# 16ChFNIRS.net
KiCad netlist of a schematic drawn in EAGLE
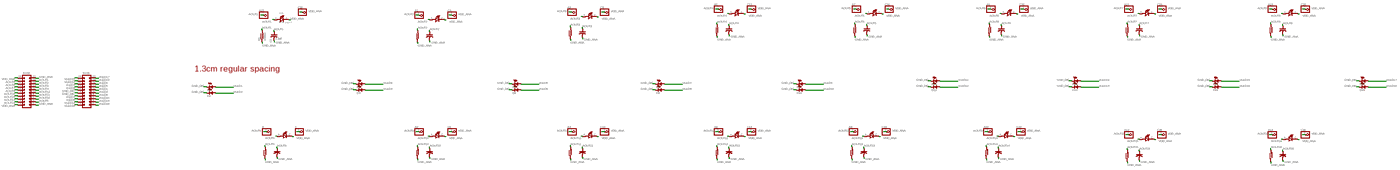
[diagram p0: schematic, sheet 1, overview]
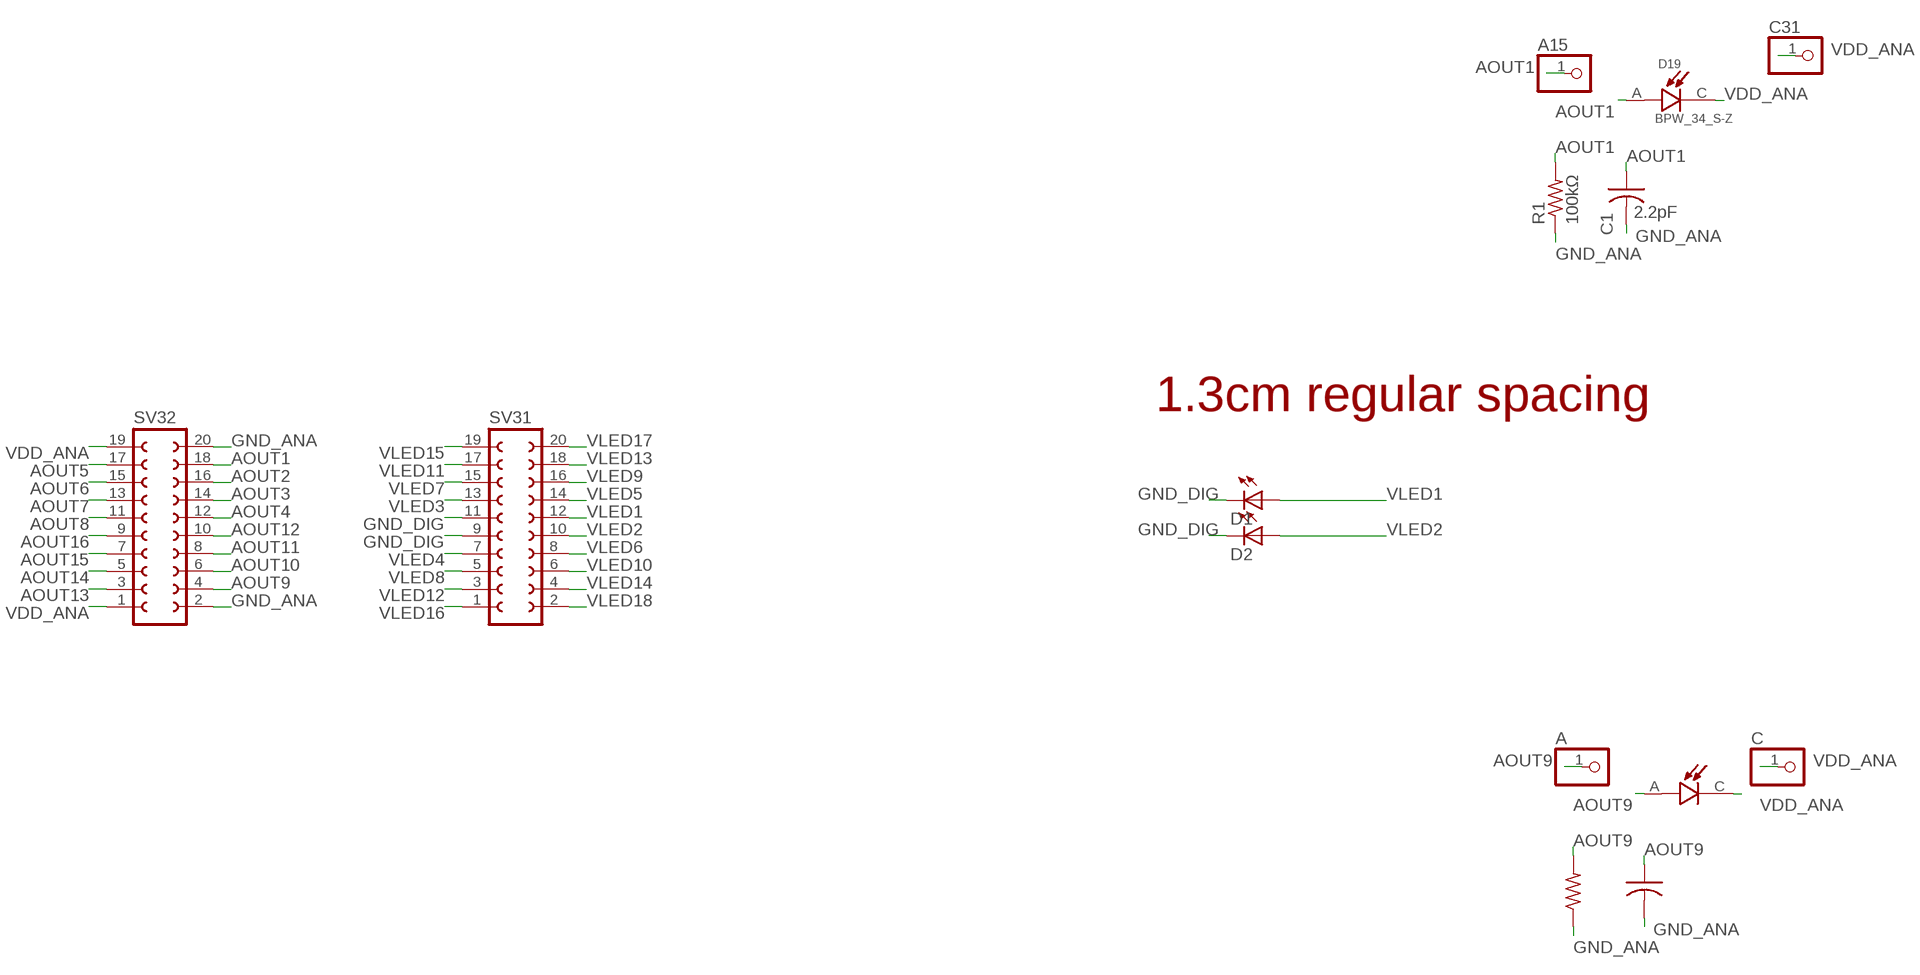
[diagram p1: schematic, sheet 1, part 1 of 4]
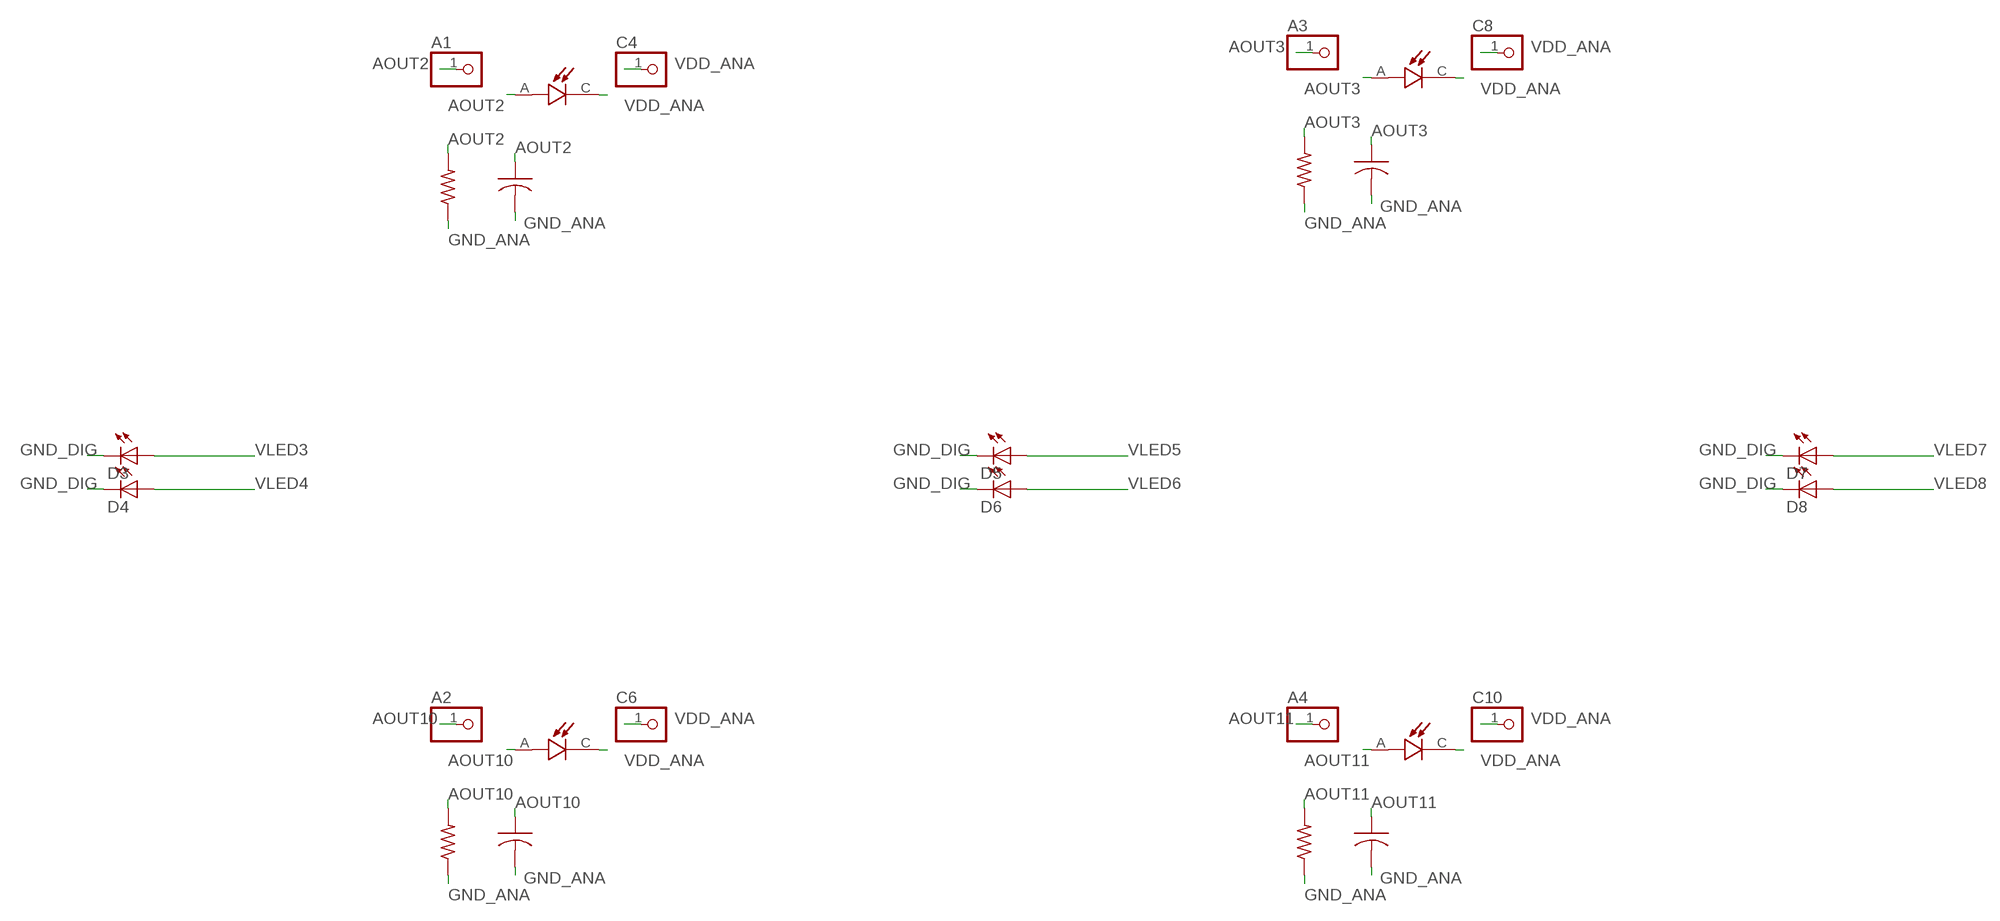
[diagram p2: schematic, sheet 1, part 2 of 4]
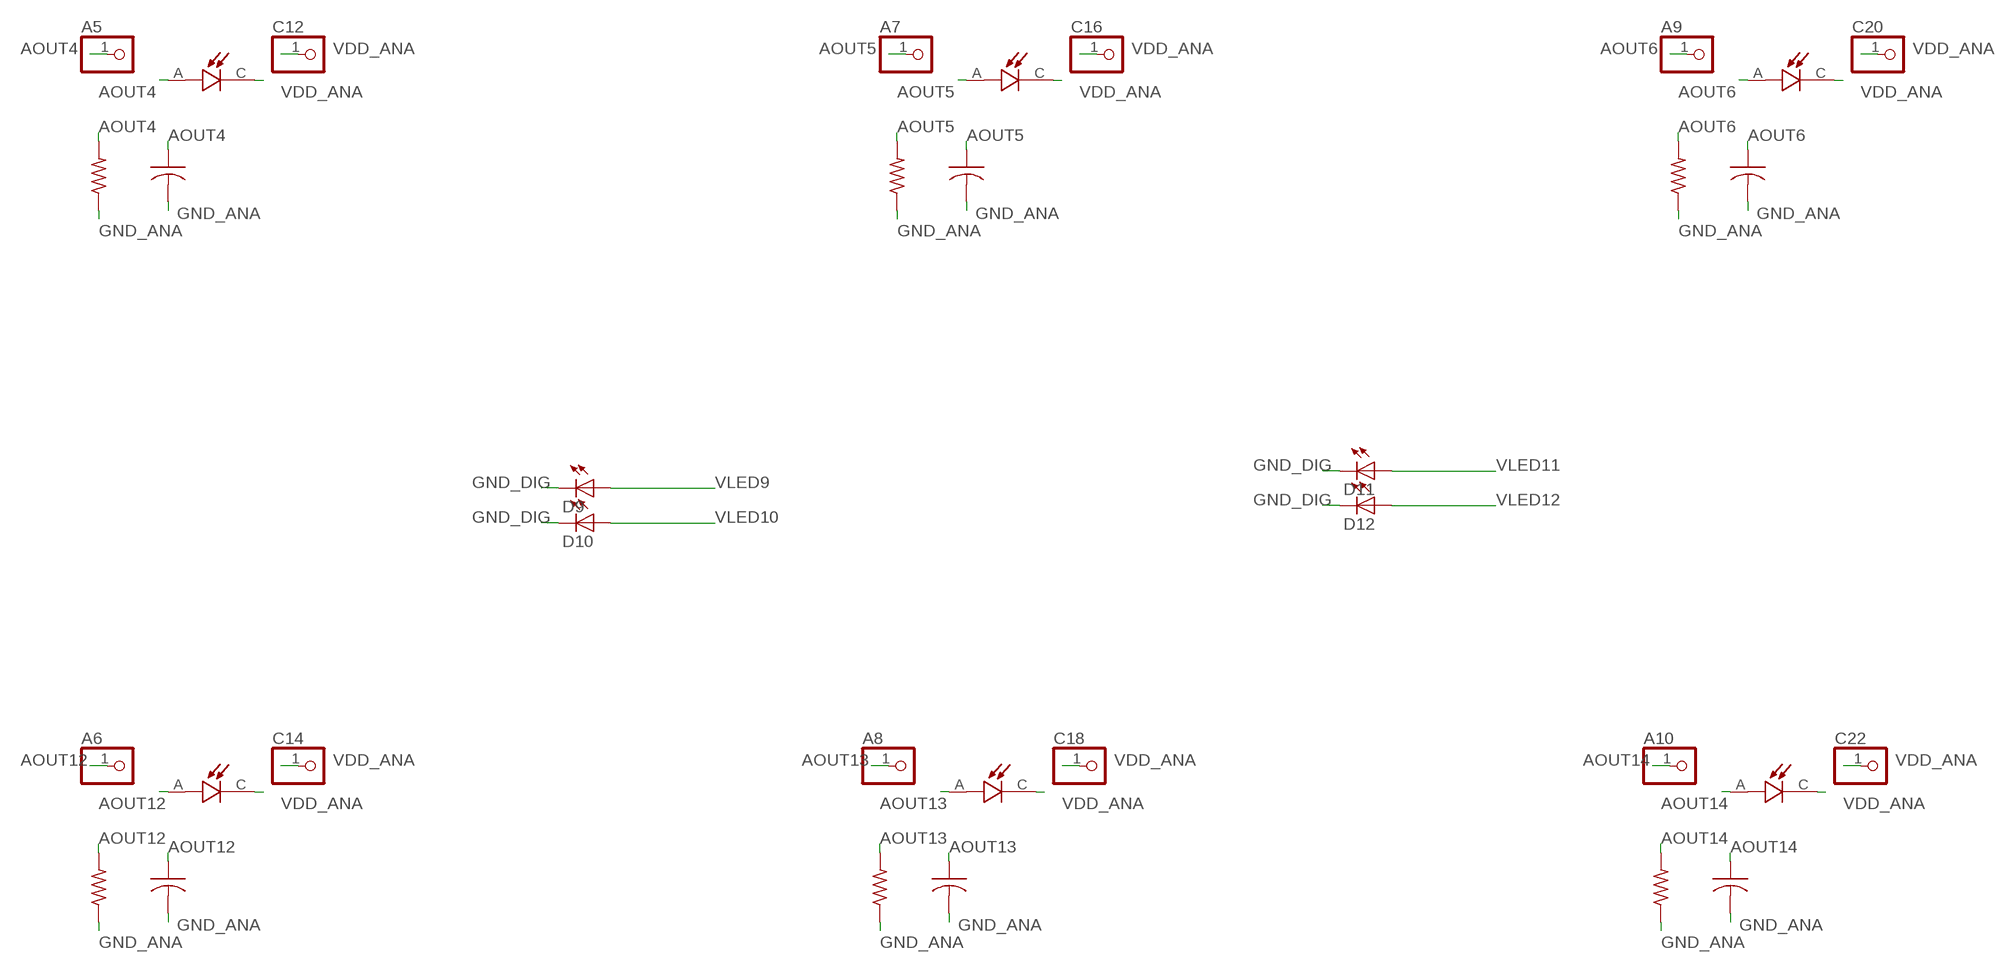
[diagram p3: schematic, sheet 1, part 3 of 4]
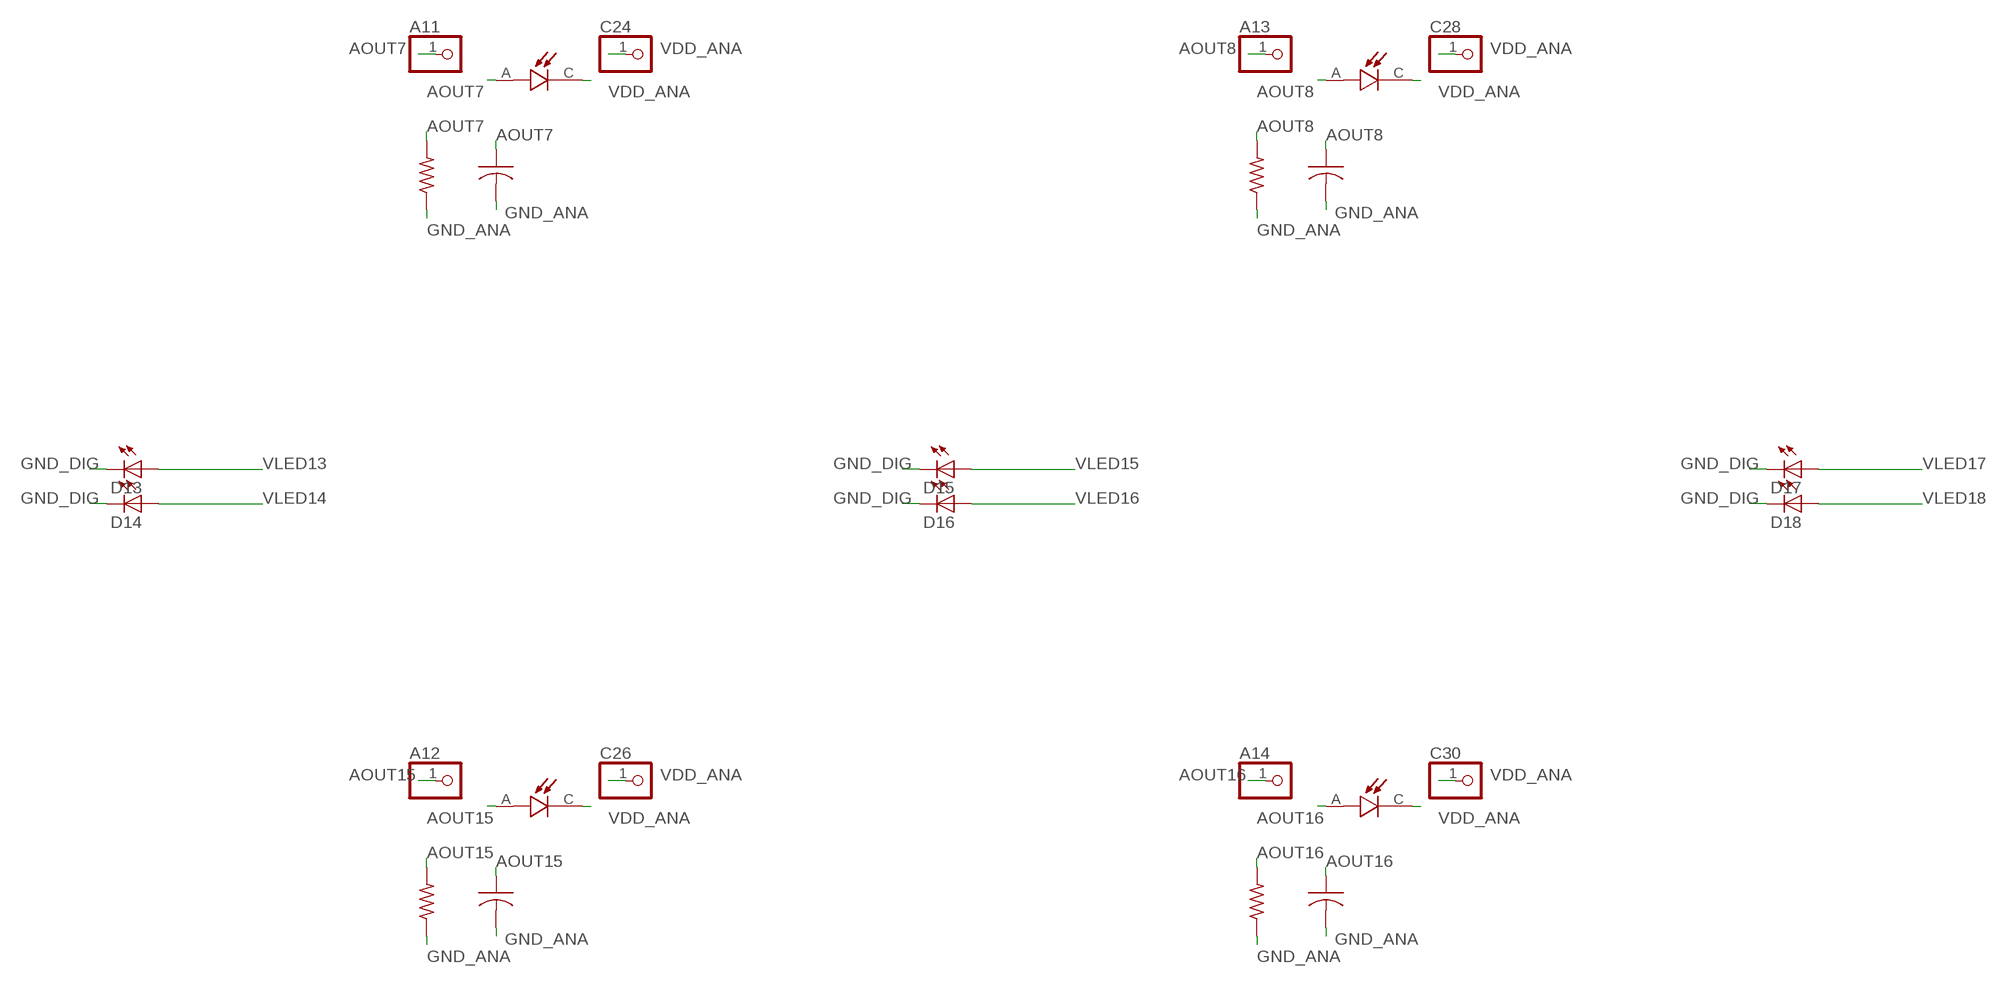
[diagram p4: schematic, sheet 1, part 4 of 4]

(export (version "E")
  (design (tool "Eeschema 10.0.6"))
  (components
    (comp (ref "A")
      (value "PINHD-1X1")
      (footprint "eagle-import:1X01")
      (libsource (lib "eagle-import") (part "PINHD-1X1"))
    )
    (comp (ref "A1")
      (value "PINHD-1X1")
      (footprint "eagle-import:1X01")
      (libsource (lib "eagle-import") (part "PINHD-1X1"))
    )
    (comp (ref "A2")
      (value "PINHD-1X1")
      (footprint "eagle-import:1X01")
      (libsource (lib "eagle-import") (part "PINHD-1X1"))
    )
    (comp (ref "A3")
      (value "PINHD-1X1")
      (footprint "eagle-import:1X01")
      (libsource (lib "eagle-import") (part "PINHD-1X1"))
    )
    (comp (ref "A4")
      (value "PINHD-1X1")
      (footprint "eagle-import:1X01")
      (libsource (lib "eagle-import") (part "PINHD-1X1"))
    )
    (comp (ref "A5")
      (value "PINHD-1X1")
      (footprint "eagle-import:1X01")
      (libsource (lib "eagle-import") (part "PINHD-1X1"))
    )
    (comp (ref "A6")
      (value "PINHD-1X1")
      (footprint "eagle-import:1X01")
      (libsource (lib "eagle-import") (part "PINHD-1X1"))
    )
    (comp (ref "A7")
      (value "PINHD-1X1")
      (footprint "eagle-import:1X01")
      (libsource (lib "eagle-import") (part "PINHD-1X1"))
    )
    (comp (ref "A8")
      (value "PINHD-1X1")
      (footprint "eagle-import:1X01")
      (libsource (lib "eagle-import") (part "PINHD-1X1"))
    )
    (comp (ref "A9")
      (value "PINHD-1X1")
      (footprint "eagle-import:1X01")
      (libsource (lib "eagle-import") (part "PINHD-1X1"))
    )
    (comp (ref "A10")
      (value "PINHD-1X1")
      (footprint "eagle-import:1X01")
      (libsource (lib "eagle-import") (part "PINHD-1X1"))
    )
    (comp (ref "A11")
      (value "PINHD-1X1")
      (footprint "eagle-import:1X01")
      (libsource (lib "eagle-import") (part "PINHD-1X1"))
    )
    (comp (ref "A12")
      (value "PINHD-1X1")
      (footprint "eagle-import:1X01")
      (libsource (lib "eagle-import") (part "PINHD-1X1"))
    )
    (comp (ref "A13")
      (value "PINHD-1X1")
      (footprint "eagle-import:1X01")
      (libsource (lib "eagle-import") (part "PINHD-1X1"))
    )
    (comp (ref "A14")
      (value "PINHD-1X1")
      (footprint "eagle-import:1X01")
      (libsource (lib "eagle-import") (part "PINHD-1X1"))
    )
    (comp (ref "A15")
      (value "PINHD-1X1")
      (footprint "eagle-import:1X01")
      (libsource (lib "eagle-import") (part "PINHD-1X1"))
    )
    (comp (ref "C")
      (value "PINHD-1X1")
      (footprint "eagle-import:1X01")
      (libsource (lib "eagle-import") (part "PINHD-1X1"))
    )
    (comp (ref "C1")
      (value "2.2pF")
      (footprint "eagle-import:C025-024X044")
      (libsource (lib "eagle-import") (part "C-US025-024X044"))
    )
    (comp (ref "C2")
      (value "2.2pF")
      (footprint "eagle-import:C025-024X044")
      (libsource (lib "eagle-import") (part "C-US025-024X044"))
    )
    (comp (ref "C3")
      (value "2.2pF")
      (footprint "eagle-import:C025-024X044")
      (libsource (lib "eagle-import") (part "C-US025-024X044"))
    )
    (comp (ref "C4")
      (value "PINHD-1X1")
      (footprint "eagle-import:1X01")
      (libsource (lib "eagle-import") (part "PINHD-1X1"))
    )
    (comp (ref "C5")
      (value "2.2pF")
      (footprint "eagle-import:C025-024X044")
      (libsource (lib "eagle-import") (part "C-US025-024X044"))
    )
    (comp (ref "C6")
      (value "PINHD-1X1")
      (footprint "eagle-import:1X01")
      (libsource (lib "eagle-import") (part "PINHD-1X1"))
    )
    (comp (ref "C7")
      (value "2.2pF")
      (footprint "eagle-import:C025-024X044")
      (libsource (lib "eagle-import") (part "C-US025-024X044"))
    )
    (comp (ref "C8")
      (value "PINHD-1X1")
      (footprint "eagle-import:1X01")
      (libsource (lib "eagle-import") (part "PINHD-1X1"))
    )
    (comp (ref "C9")
      (value "2.2pF")
      (footprint "eagle-import:C025-024X044")
      (libsource (lib "eagle-import") (part "C-US025-024X044"))
    )
    (comp (ref "C10")
      (value "PINHD-1X1")
      (footprint "eagle-import:1X01")
      (libsource (lib "eagle-import") (part "PINHD-1X1"))
    )
    (comp (ref "C11")
      (value "2.2pF")
      (footprint "eagle-import:C025-024X044")
      (libsource (lib "eagle-import") (part "C-US025-024X044"))
    )
    (comp (ref "C12")
      (value "PINHD-1X1")
      (footprint "eagle-import:1X01")
      (libsource (lib "eagle-import") (part "PINHD-1X1"))
    )
    (comp (ref "C13")
      (value "2.2pF")
      (footprint "eagle-import:C025-024X044")
      (libsource (lib "eagle-import") (part "C-US025-024X044"))
    )
    (comp (ref "C14")
      (value "PINHD-1X1")
      (footprint "eagle-import:1X01")
      (libsource (lib "eagle-import") (part "PINHD-1X1"))
    )
    (comp (ref "C15")
      (value "2.2pF")
      (footprint "eagle-import:C025-024X044")
      (libsource (lib "eagle-import") (part "C-US025-024X044"))
    )
    (comp (ref "C16")
      (value "PINHD-1X1")
      (footprint "eagle-import:1X01")
      (libsource (lib "eagle-import") (part "PINHD-1X1"))
    )
    (comp (ref "C17")
      (value "2.2pF")
      (footprint "eagle-import:C025-024X044")
      (libsource (lib "eagle-import") (part "C-US025-024X044"))
    )
    (comp (ref "C18")
      (value "PINHD-1X1")
      (footprint "eagle-import:1X01")
      (libsource (lib "eagle-import") (part "PINHD-1X1"))
    )
    (comp (ref "C19")
      (value "2.2pF")
      (footprint "eagle-import:C025-024X044")
      (libsource (lib "eagle-import") (part "C-US025-024X044"))
    )
    (comp (ref "C20")
      (value "PINHD-1X1")
      (footprint "eagle-import:1X01")
      (libsource (lib "eagle-import") (part "PINHD-1X1"))
    )
    (comp (ref "C21")
      (value "2.2pF")
      (footprint "eagle-import:C025-024X044")
      (libsource (lib "eagle-import") (part "C-US025-024X044"))
    )
    (comp (ref "C22")
      (value "PINHD-1X1")
      (footprint "eagle-import:1X01")
      (libsource (lib "eagle-import") (part "PINHD-1X1"))
    )
    (comp (ref "C23")
      (value "2.2pF")
      (footprint "eagle-import:C025-024X044")
      (libsource (lib "eagle-import") (part "C-US025-024X044"))
    )
    (comp (ref "C24")
      (value "PINHD-1X1")
      (footprint "eagle-import:1X01")
      (libsource (lib "eagle-import") (part "PINHD-1X1"))
    )
    (comp (ref "C25")
      (value "2.2pF")
      (footprint "eagle-import:C025-024X044")
      (libsource (lib "eagle-import") (part "C-US025-024X044"))
    )
    (comp (ref "C26")
      (value "PINHD-1X1")
      (footprint "eagle-import:1X01")
      (libsource (lib "eagle-import") (part "PINHD-1X1"))
    )
    (comp (ref "C27")
      (value "2.2pF")
      (footprint "eagle-import:C025-024X044")
      (libsource (lib "eagle-import") (part "C-US025-024X044"))
    )
    (comp (ref "C28")
      (value "PINHD-1X1")
      (footprint "eagle-import:1X01")
      (libsource (lib "eagle-import") (part "PINHD-1X1"))
    )
    (comp (ref "C29")
      (value "2.2pF")
      (footprint "eagle-import:C025-024X044")
      (libsource (lib "eagle-import") (part "C-US025-024X044"))
    )
    (comp (ref "C30")
      (value "PINHD-1X1")
      (footprint "eagle-import:1X01")
      (libsource (lib "eagle-import") (part "PINHD-1X1"))
    )
    (comp (ref "C31")
      (value "PINHD-1X1")
      (footprint "eagle-import:1X01")
      (libsource (lib "eagle-import") (part "PINHD-1X1"))
    )
    (comp (ref "D1")
      (value "LED1206")
      (footprint "eagle-import:LED-1206")
      (libsource (lib "eagle-import") (part "LED1206"))
    )
    (comp (ref "D2")
      (value "LED1206")
      (footprint "eagle-import:LED-1206")
      (libsource (lib "eagle-import") (part "LED1206"))
    )
    (comp (ref "D3")
      (value "LED1206")
      (footprint "eagle-import:LED-1206")
      (libsource (lib "eagle-import") (part "LED1206"))
    )
    (comp (ref "D4")
      (value "LED1206")
      (footprint "eagle-import:LED-1206")
      (libsource (lib "eagle-import") (part "LED1206"))
    )
    (comp (ref "D5")
      (value "LED1206")
      (footprint "eagle-import:LED-1206")
      (libsource (lib "eagle-import") (part "LED1206"))
    )
    (comp (ref "D6")
      (value "LED1206")
      (footprint "eagle-import:LED-1206")
      (libsource (lib "eagle-import") (part "LED1206"))
    )
    (comp (ref "D7")
      (value "LED1206")
      (footprint "eagle-import:LED-1206")
      (libsource (lib "eagle-import") (part "LED1206"))
    )
    (comp (ref "D8")
      (value "LED1206")
      (footprint "eagle-import:LED-1206")
      (libsource (lib "eagle-import") (part "LED1206"))
    )
    (comp (ref "D9")
      (value "LED1206")
      (footprint "eagle-import:LED-1206")
      (libsource (lib "eagle-import") (part "LED1206"))
    )
    (comp (ref "D10")
      (value "LED1206")
      (footprint "eagle-import:LED-1206")
      (libsource (lib "eagle-import") (part "LED1206"))
    )
    (comp (ref "D11")
      (value "LED1206")
      (footprint "eagle-import:LED-1206")
      (libsource (lib "eagle-import") (part "LED1206"))
    )
    (comp (ref "D12")
      (value "LED1206")
      (footprint "eagle-import:LED-1206")
      (libsource (lib "eagle-import") (part "LED1206"))
    )
    (comp (ref "D13")
      (value "LED1206")
      (footprint "eagle-import:LED-1206")
      (libsource (lib "eagle-import") (part "LED1206"))
    )
    (comp (ref "D14")
      (value "LED1206")
      (footprint "eagle-import:LED-1206")
      (libsource (lib "eagle-import") (part "LED1206"))
    )
    (comp (ref "D15")
      (value "LED1206")
      (footprint "eagle-import:LED-1206")
      (libsource (lib "eagle-import") (part "LED1206"))
    )
    (comp (ref "D16")
      (value "LED1206")
      (footprint "eagle-import:LED-1206")
      (libsource (lib "eagle-import") (part "LED1206"))
    )
    (comp (ref "D17")
      (value "LED1206")
      (footprint "eagle-import:LED-1206")
      (libsource (lib "eagle-import") (part "LED1206"))
    )
    (comp (ref "D18")
      (value "LED1206")
      (footprint "eagle-import:LED-1206")
      (libsource (lib "eagle-import") (part "LED1206"))
    )
    (comp (ref "D19")
      (value "BPW_34_S-Z")
      (footprint "eagle-import:DIO_BPW_34_S-Z")
      (fields (field (name "MF") "OSRAM Opto") (field (name "MP") "BPW 34 S-Z"))
      (libsource (lib "eagle-import") (part "BPW_34_S-Z"))
    )
    (comp (ref "D20")
      (value "BPW_34_S-Z")
      (footprint "eagle-import:DIO_BPW_34_S-Z")
      (fields (field (name "MF") "OSRAM Opto") (field (name "MP") "BPW 34 S-Z"))
      (libsource (lib "eagle-import") (part "BPW_34_S-Z"))
    )
    (comp (ref "D21")
      (value "BPW_34_S-Z")
      (footprint "eagle-import:DIO_BPW_34_S-Z")
      (fields (field (name "MF") "OSRAM Opto") (field (name "MP") "BPW 34 S-Z"))
      (libsource (lib "eagle-import") (part "BPW_34_S-Z"))
    )
    (comp (ref "D22")
      (value "BPW_34_S-Z")
      (footprint "eagle-import:DIO_BPW_34_S-Z")
      (fields (field (name "MF") "OSRAM Opto") (field (name "MP") "BPW 34 S-Z"))
      (libsource (lib "eagle-import") (part "BPW_34_S-Z"))
    )
    (comp (ref "D23")
      (value "BPW_34_S-Z")
      (footprint "eagle-import:DIO_BPW_34_S-Z")
      (fields (field (name "MF") "OSRAM Opto") (field (name "MP") "BPW 34 S-Z"))
      (libsource (lib "eagle-import") (part "BPW_34_S-Z"))
    )
    (comp (ref "D24")
      (value "BPW_34_S-Z")
      (footprint "eagle-import:DIO_BPW_34_S-Z")
      (fields (field (name "MF") "OSRAM Opto") (field (name "MP") "BPW 34 S-Z"))
      (libsource (lib "eagle-import") (part "BPW_34_S-Z"))
    )
    (comp (ref "D25")
      (value "BPW_34_S-Z")
      (footprint "eagle-import:DIO_BPW_34_S-Z")
      (fields (field (name "MF") "OSRAM Opto") (field (name "MP") "BPW 34 S-Z"))
      (libsource (lib "eagle-import") (part "BPW_34_S-Z"))
    )
    (comp (ref "D26")
      (value "BPW_34_S-Z")
      (footprint "eagle-import:DIO_BPW_34_S-Z")
      (fields (field (name "MF") "OSRAM Opto") (field (name "MP") "BPW 34 S-Z"))
      (libsource (lib "eagle-import") (part "BPW_34_S-Z"))
    )
    (comp (ref "D27")
      (value "BPW_34_S-Z")
      (footprint "eagle-import:DIO_BPW_34_S-Z")
      (fields (field (name "MF") "OSRAM Opto") (field (name "MP") "BPW 34 S-Z"))
      (libsource (lib "eagle-import") (part "BPW_34_S-Z"))
    )
    (comp (ref "D28")
      (value "BPW_34_S-Z")
      (footprint "eagle-import:DIO_BPW_34_S-Z")
      (fields (field (name "MF") "OSRAM Opto") (field (name "MP") "BPW 34 S-Z"))
      (libsource (lib "eagle-import") (part "BPW_34_S-Z"))
    )
    (comp (ref "D29")
      (value "BPW_34_S-Z")
      (footprint "eagle-import:DIO_BPW_34_S-Z")
      (fields (field (name "MF") "OSRAM Opto") (field (name "MP") "BPW 34 S-Z"))
      (libsource (lib "eagle-import") (part "BPW_34_S-Z"))
    )
    (comp (ref "D30")
      (value "BPW_34_S-Z")
      (footprint "eagle-import:DIO_BPW_34_S-Z")
      (fields (field (name "MF") "OSRAM Opto") (field (name "MP") "BPW 34 S-Z"))
      (libsource (lib "eagle-import") (part "BPW_34_S-Z"))
    )
    (comp (ref "D31")
      (value "BPW_34_S-Z")
      (footprint "eagle-import:DIO_BPW_34_S-Z")
      (fields (field (name "MF") "OSRAM Opto") (field (name "MP") "BPW 34 S-Z"))
      (libsource (lib "eagle-import") (part "BPW_34_S-Z"))
    )
    (comp (ref "D32")
      (value "BPW_34_S-Z")
      (footprint "eagle-import:DIO_BPW_34_S-Z")
      (fields (field (name "MF") "OSRAM Opto") (field (name "MP") "BPW 34 S-Z"))
      (libsource (lib "eagle-import") (part "BPW_34_S-Z"))
    )
    (comp (ref "D33")
      (value "BPW_34_S-Z")
      (footprint "eagle-import:DIO_BPW_34_S-Z")
      (fields (field (name "MF") "OSRAM Opto") (field (name "MP") "BPW 34 S-Z"))
      (libsource (lib "eagle-import") (part "BPW_34_S-Z"))
    )
    (comp (ref "D34")
      (value "BPW_34_S-Z")
      (footprint "eagle-import:DIO_BPW_34_S-Z")
      (fields (field (name "MF") "OSRAM Opto") (field (name "MP") "BPW 34 S-Z"))
      (libsource (lib "eagle-import") (part "BPW_34_S-Z"))
    )
    (comp (ref "R1")
      (value "100kΩ")
      (footprint "eagle-import:0204_5")
      (libsource (lib "eagle-import") (part "R-US_0204/5"))
    )
    (comp (ref "R2")
      (value "100kΩ")
      (footprint "eagle-import:0204_5")
      (libsource (lib "eagle-import") (part "R-US_0204/5"))
    )
    (comp (ref "R3")
      (value "100kΩ")
      (footprint "eagle-import:0204_5")
      (libsource (lib "eagle-import") (part "R-US_0204/5"))
    )
    (comp (ref "R4")
      (value "100kΩ")
      (footprint "eagle-import:0204_5")
      (libsource (lib "eagle-import") (part "R-US_0204/5"))
    )
    (comp (ref "R5")
      (value "100kΩ")
      (footprint "eagle-import:0204_5")
      (libsource (lib "eagle-import") (part "R-US_0204/5"))
    )
    (comp (ref "R6")
      (value "100kΩ")
      (footprint "eagle-import:0204_5")
      (libsource (lib "eagle-import") (part "R-US_0204/5"))
    )
    (comp (ref "R7")
      (value "100kΩ")
      (footprint "eagle-import:0204_5")
      (libsource (lib "eagle-import") (part "R-US_0204/5"))
    )
    (comp (ref "R8")
      (value "100kΩ")
      (footprint "eagle-import:0204_5")
      (libsource (lib "eagle-import") (part "R-US_0204/5"))
    )
    (comp (ref "R9")
      (value "100kΩ")
      (footprint "eagle-import:0204_5")
      (libsource (lib "eagle-import") (part "R-US_0204/5"))
    )
    (comp (ref "R10")
      (value "100kΩ")
      (footprint "eagle-import:0204_5")
      (libsource (lib "eagle-import") (part "R-US_0204/5"))
    )
    (comp (ref "R11")
      (value "100kΩ")
      (footprint "eagle-import:0204_5")
      (libsource (lib "eagle-import") (part "R-US_0204/5"))
    )
    (comp (ref "R12")
      (value "100kΩ")
      (footprint "eagle-import:0204_5")
      (libsource (lib "eagle-import") (part "R-US_0204/5"))
    )
    (comp (ref "R13")
      (value "100kΩ")
      (footprint "eagle-import:0204_5")
      (libsource (lib "eagle-import") (part "R-US_0204/5"))
    )
    (comp (ref "R14")
      (value "100kΩ")
      (footprint "eagle-import:0204_5")
      (libsource (lib "eagle-import") (part "R-US_0204/5"))
    )
    (comp (ref "R15")
      (value "100kΩ")
      (footprint "eagle-import:0204_5")
      (libsource (lib "eagle-import") (part "R-US_0204/5"))
    )
    (comp (ref "R16")
      (value "100kΩ")
      (footprint "eagle-import:0204_5")
      (libsource (lib "eagle-import") (part "R-US_0204/5"))
    )
    (comp (ref "SV31")
      (value "FE10-2")
      (footprint "eagle-import:FE10-2")
      (libsource (lib "eagle-import") (part "FE10-2"))
    )
    (comp (ref "SV32")
      (value "FE10-2")
      (footprint "eagle-import:FE10-2")
      (libsource (lib "eagle-import") (part "FE10-2"))
    )
  )
  (nets
    (net (code "1") (name "/AOUT1") (class "Default")
      (node (ref "A15") (pin "1") (pinfunction "1_1") (pintype "passive"))
      (node (ref "C1") (pin "1") (pinfunction "1_1") (pintype "passive"))
      (node (ref "D19") (pin "A") (pinfunction "A_A") (pintype "passive"))
      (node (ref "R1") (pin "2") (pinfunction "2_2") (pintype "passive"))
      (node (ref "SV32") (pin "18") (pinfunction "18_18") (pintype "passive"))
    )
    (net (code "2") (name "/AOUT2") (class "Default")
      (node (ref "A1") (pin "1") (pinfunction "1_1") (pintype "passive"))
      (node (ref "C3") (pin "1") (pinfunction "1_1") (pintype "passive"))
      (node (ref "D21") (pin "A") (pinfunction "A_A") (pintype "passive"))
      (node (ref "R3") (pin "2") (pinfunction "2_2") (pintype "passive"))
      (node (ref "SV32") (pin "16") (pinfunction "16_16") (pintype "passive"))
    )
    (net (code "3") (name "/AOUT3") (class "Default")
      (node (ref "A3") (pin "1") (pinfunction "1_1") (pintype "passive"))
      (node (ref "C7") (pin "1") (pinfunction "1_1") (pintype "passive"))
      (node (ref "D23") (pin "A") (pinfunction "A_A") (pintype "passive"))
      (node (ref "R5") (pin "2") (pinfunction "2_2") (pintype "passive"))
      (node (ref "SV32") (pin "14") (pinfunction "14_14") (pintype "passive"))
    )
    (net (code "4") (name "/AOUT4") (class "Default")
      (node (ref "A5") (pin "1") (pinfunction "1_1") (pintype "passive"))
      (node (ref "C11") (pin "1") (pinfunction "1_1") (pintype "passive"))
      (node (ref "D25") (pin "A") (pinfunction "A_A") (pintype "passive"))
      (node (ref "R7") (pin "2") (pinfunction "2_2") (pintype "passive"))
      (node (ref "SV32") (pin "12") (pinfunction "12_12") (pintype "passive"))
    )
    (net (code "5") (name "/AOUT5") (class "Default")
      (node (ref "A7") (pin "1") (pinfunction "1_1") (pintype "passive"))
      (node (ref "C15") (pin "1") (pinfunction "1_1") (pintype "passive"))
      (node (ref "D27") (pin "A") (pinfunction "A_A") (pintype "passive"))
      (node (ref "R9") (pin "2") (pinfunction "2_2") (pintype "passive"))
      (node (ref "SV32") (pin "17") (pinfunction "17_17") (pintype "passive"))
    )
    (net (code "6") (name "/AOUT6") (class "Default")
      (node (ref "A9") (pin "1") (pinfunction "1_1") (pintype "passive"))
      (node (ref "C19") (pin "1") (pinfunction "1_1") (pintype "passive"))
      (node (ref "D29") (pin "A") (pinfunction "A_A") (pintype "passive"))
      (node (ref "R11") (pin "2") (pinfunction "2_2") (pintype "passive"))
      (node (ref "SV32") (pin "15") (pinfunction "15_15") (pintype "passive"))
    )
    (net (code "7") (name "/AOUT7") (class "Default")
      (node (ref "A11") (pin "1") (pinfunction "1_1") (pintype "passive"))
      (node (ref "C23") (pin "1") (pinfunction "1_1") (pintype "passive"))
      (node (ref "D31") (pin "A") (pinfunction "A_A") (pintype "passive"))
      (node (ref "R13") (pin "2") (pinfunction "2_2") (pintype "passive"))
      (node (ref "SV32") (pin "13") (pinfunction "13_13") (pintype "passive"))
    )
    (net (code "8") (name "/AOUT8") (class "Default")
      (node (ref "A13") (pin "1") (pinfunction "1_1") (pintype "passive"))
      (node (ref "C27") (pin "1") (pinfunction "1_1") (pintype "passive"))
      (node (ref "D33") (pin "A") (pinfunction "A_A") (pintype "passive"))
      (node (ref "R15") (pin "2") (pinfunction "2_2") (pintype "passive"))
      (node (ref "SV32") (pin "11") (pinfunction "11_11") (pintype "passive"))
    )
    (net (code "9") (name "/AOUT9") (class "Default")
      (node (ref "A") (pin "1") (pinfunction "1_1") (pintype "passive"))
      (node (ref "C2") (pin "1") (pinfunction "1_1") (pintype "passive"))
      (node (ref "D20") (pin "A") (pinfunction "A_A") (pintype "passive"))
      (node (ref "R2") (pin "2") (pinfunction "2_2") (pintype "passive"))
      (node (ref "SV32") (pin "4") (pinfunction "4_4") (pintype "passive"))
    )
    (net (code "10") (name "/AOUT10") (class "Default")
      (node (ref "A2") (pin "1") (pinfunction "1_1") (pintype "passive"))
      (node (ref "C5") (pin "1") (pinfunction "1_1") (pintype "passive"))
      (node (ref "D22") (pin "A") (pinfunction "A_A") (pintype "passive"))
      (node (ref "R4") (pin "2") (pinfunction "2_2") (pintype "passive"))
      (node (ref "SV32") (pin "6") (pinfunction "6_6") (pintype "passive"))
    )
    (net (code "11") (name "/AOUT11") (class "Default")
      (node (ref "A4") (pin "1") (pinfunction "1_1") (pintype "passive"))
      (node (ref "C9") (pin "1") (pinfunction "1_1") (pintype "passive"))
      (node (ref "D24") (pin "A") (pinfunction "A_A") (pintype "passive"))
      (node (ref "R6") (pin "2") (pinfunction "2_2") (pintype "passive"))
      (node (ref "SV32") (pin "8") (pinfunction "8_8") (pintype "passive"))
    )
    (net (code "12") (name "/AOUT12") (class "Default")
      (node (ref "A6") (pin "1") (pinfunction "1_1") (pintype "passive"))
      (node (ref "C13") (pin "1") (pinfunction "1_1") (pintype "passive"))
      (node (ref "D26") (pin "A") (pinfunction "A_A") (pintype "passive"))
      (node (ref "R8") (pin "2") (pinfunction "2_2") (pintype "passive"))
      (node (ref "SV32") (pin "10") (pinfunction "10_10") (pintype "passive"))
    )
    (net (code "13") (name "/AOUT13") (class "Default")
      (node (ref "A8") (pin "1") (pinfunction "1_1") (pintype "passive"))
      (node (ref "C17") (pin "1") (pinfunction "1_1") (pintype "passive"))
      (node (ref "D28") (pin "A") (pinfunction "A_A") (pintype "passive"))
      (node (ref "R10") (pin "2") (pinfunction "2_2") (pintype "passive"))
      (node (ref "SV32") (pin "3") (pinfunction "3_3") (pintype "passive"))
    )
    (net (code "14") (name "/AOUT14") (class "Default")
      (node (ref "A10") (pin "1") (pinfunction "1_1") (pintype "passive"))
      (node (ref "C21") (pin "1") (pinfunction "1_1") (pintype "passive"))
      (node (ref "D30") (pin "A") (pinfunction "A_A") (pintype "passive"))
      (node (ref "R12") (pin "2") (pinfunction "2_2") (pintype "passive"))
      (node (ref "SV32") (pin "5") (pinfunction "5_5") (pintype "passive"))
    )
    (net (code "15") (name "/AOUT15") (class "Default")
      (node (ref "A12") (pin "1") (pinfunction "1_1") (pintype "passive"))
      (node (ref "C25") (pin "1") (pinfunction "1_1") (pintype "passive"))
      (node (ref "D32") (pin "A") (pinfunction "A_A") (pintype "passive"))
      (node (ref "R14") (pin "2") (pinfunction "2_2") (pintype "passive"))
      (node (ref "SV32") (pin "7") (pinfunction "7_7") (pintype "passive"))
    )
    (net (code "16") (name "/AOUT16") (class "Default")
      (node (ref "A14") (pin "1") (pinfunction "1_1") (pintype "passive"))
      (node (ref "C29") (pin "1") (pinfunction "1_1") (pintype "passive"))
      (node (ref "D34") (pin "A") (pinfunction "A_A") (pintype "passive"))
      (node (ref "R16") (pin "2") (pinfunction "2_2") (pintype "passive"))
      (node (ref "SV32") (pin "9") (pinfunction "9_9") (pintype "passive"))
    )
    (net (code "17") (name "/GND_ANA") (class "Default")
      (node (ref "C1") (pin "2") (pinfunction "2_2") (pintype "passive"))
      (node (ref "C11") (pin "2") (pinfunction "2_2") (pintype "passive"))
      (node (ref "C13") (pin "2") (pinfunction "2_2") (pintype "passive"))
      (node (ref "C15") (pin "2") (pinfunction "2_2") (pintype "passive"))
      (node (ref "C17") (pin "2") (pinfunction "2_2") (pintype "passive"))
      (node (ref "C19") (pin "2") (pinfunction "2_2") (pintype "passive"))
      (node (ref "C2") (pin "2") (pinfunction "2_2") (pintype "passive"))
      (node (ref "C21") (pin "2") (pinfunction "2_2") (pintype "passive"))
      (node (ref "C23") (pin "2") (pinfunction "2_2") (pintype "passive"))
      (node (ref "C25") (pin "2") (pinfunction "2_2") (pintype "passive"))
      (node (ref "C27") (pin "2") (pinfunction "2_2") (pintype "passive"))
      (node (ref "C29") (pin "2") (pinfunction "2_2") (pintype "passive"))
      (node (ref "C3") (pin "2") (pinfunction "2_2") (pintype "passive"))
      (node (ref "C5") (pin "2") (pinfunction "2_2") (pintype "passive"))
      (node (ref "C7") (pin "2") (pinfunction "2_2") (pintype "passive"))
      (node (ref "C9") (pin "2") (pinfunction "2_2") (pintype "passive"))
      (node (ref "R1") (pin "1") (pinfunction "1_1") (pintype "passive"))
      (node (ref "R10") (pin "1") (pinfunction "1_1") (pintype "passive"))
      (node (ref "R11") (pin "1") (pinfunction "1_1") (pintype "passive"))
      (node (ref "R12") (pin "1") (pinfunction "1_1") (pintype "passive"))
      (node (ref "R13") (pin "1") (pinfunction "1_1") (pintype "passive"))
      (node (ref "R14") (pin "1") (pinfunction "1_1") (pintype "passive"))
      (node (ref "R15") (pin "1") (pinfunction "1_1") (pintype "passive"))
      (node (ref "R16") (pin "1") (pinfunction "1_1") (pintype "passive"))
      (node (ref "R2") (pin "1") (pinfunction "1_1") (pintype "passive"))
      (node (ref "R3") (pin "1") (pinfunction "1_1") (pintype "passive"))
      (node (ref "R4") (pin "1") (pinfunction "1_1") (pintype "passive"))
      (node (ref "R5") (pin "1") (pinfunction "1_1") (pintype "passive"))
      (node (ref "R6") (pin "1") (pinfunction "1_1") (pintype "passive"))
      (node (ref "R7") (pin "1") (pinfunction "1_1") (pintype "passive"))
      (node (ref "R8") (pin "1") (pinfunction "1_1") (pintype "passive"))
      (node (ref "R9") (pin "1") (pinfunction "1_1") (pintype "passive"))
      (node (ref "SV32") (pin "2") (pinfunction "2_2") (pintype "passive"))
      (node (ref "SV32") (pin "20") (pinfunction "20_20") (pintype "passive"))
    )
    (net (code "18") (name "/GND_DIG") (class "Default")
      (node (ref "D1") (pin "C") (pinfunction "C_C") (pintype "passive"))
      (node (ref "D10") (pin "C") (pinfunction "C_C") (pintype "passive"))
      (node (ref "D11") (pin "C") (pinfunction "C_C") (pintype "passive"))
      (node (ref "D12") (pin "C") (pinfunction "C_C") (pintype "passive"))
      (node (ref "D13") (pin "C") (pinfunction "C_C") (pintype "passive"))
      (node (ref "D14") (pin "C") (pinfunction "C_C") (pintype "passive"))
      (node (ref "D15") (pin "C") (pinfunction "C_C") (pintype "passive"))
      (node (ref "D16") (pin "C") (pinfunction "C_C") (pintype "passive"))
      (node (ref "D17") (pin "C") (pinfunction "C_C") (pintype "passive"))
      (node (ref "D18") (pin "C") (pinfunction "C_C") (pintype "passive"))
      (node (ref "D2") (pin "C") (pinfunction "C_C") (pintype "passive"))
      (node (ref "D3") (pin "C") (pinfunction "C_C") (pintype "passive"))
      (node (ref "D4") (pin "C") (pinfunction "C_C") (pintype "passive"))
      (node (ref "D5") (pin "C") (pinfunction "C_C") (pintype "passive"))
      (node (ref "D6") (pin "C") (pinfunction "C_C") (pintype "passive"))
      (node (ref "D7") (pin "C") (pinfunction "C_C") (pintype "passive"))
      (node (ref "D8") (pin "C") (pinfunction "C_C") (pintype "passive"))
      (node (ref "D9") (pin "C") (pinfunction "C_C") (pintype "passive"))
      (node (ref "SV31") (pin "11") (pinfunction "11_11") (pintype "passive"))
      (node (ref "SV31") (pin "9") (pinfunction "9_9") (pintype "passive"))
    )
    (net (code "19") (name "/VDD_ANA") (class "Default")
      (node (ref "C") (pin "1") (pinfunction "1_1") (pintype "passive"))
      (node (ref "C10") (pin "1") (pinfunction "1_1") (pintype "passive"))
      (node (ref "C12") (pin "1") (pinfunction "1_1") (pintype "passive"))
      (node (ref "C14") (pin "1") (pinfunction "1_1") (pintype "passive"))
      (node (ref "C16") (pin "1") (pinfunction "1_1") (pintype "passive"))
      (node (ref "C18") (pin "1") (pinfunction "1_1") (pintype "passive"))
      (node (ref "C20") (pin "1") (pinfunction "1_1") (pintype "passive"))
      (node (ref "C22") (pin "1") (pinfunction "1_1") (pintype "passive"))
      (node (ref "C24") (pin "1") (pinfunction "1_1") (pintype "passive"))
      (node (ref "C26") (pin "1") (pinfunction "1_1") (pintype "passive"))
      (node (ref "C28") (pin "1") (pinfunction "1_1") (pintype "passive"))
      (node (ref "C30") (pin "1") (pinfunction "1_1") (pintype "passive"))
      (node (ref "C31") (pin "1") (pinfunction "1_1") (pintype "passive"))
      (node (ref "C4") (pin "1") (pinfunction "1_1") (pintype "passive"))
      (node (ref "C6") (pin "1") (pinfunction "1_1") (pintype "passive"))
      (node (ref "C8") (pin "1") (pinfunction "1_1") (pintype "passive"))
      (node (ref "D19") (pin "C") (pinfunction "C_C") (pintype "passive"))
      (node (ref "D20") (pin "C") (pinfunction "C_C") (pintype "passive"))
      (node (ref "D21") (pin "C") (pinfunction "C_C") (pintype "passive"))
      (node (ref "D22") (pin "C") (pinfunction "C_C") (pintype "passive"))
      (node (ref "D23") (pin "C") (pinfunction "C_C") (pintype "passive"))
      (node (ref "D24") (pin "C") (pinfunction "C_C") (pintype "passive"))
      (node (ref "D25") (pin "C") (pinfunction "C_C") (pintype "passive"))
      (node (ref "D26") (pin "C") (pinfunction "C_C") (pintype "passive"))
      (node (ref "D27") (pin "C") (pinfunction "C_C") (pintype "passive"))
      (node (ref "D28") (pin "C") (pinfunction "C_C") (pintype "passive"))
      (node (ref "D29") (pin "C") (pinfunction "C_C") (pintype "passive"))
      (node (ref "D30") (pin "C") (pinfunction "C_C") (pintype "passive"))
      (node (ref "D31") (pin "C") (pinfunction "C_C") (pintype "passive"))
      (node (ref "D32") (pin "C") (pinfunction "C_C") (pintype "passive"))
      (node (ref "D33") (pin "C") (pinfunction "C_C") (pintype "passive"))
      (node (ref "D34") (pin "C") (pinfunction "C_C") (pintype "passive"))
      (node (ref "SV32") (pin "1") (pinfunction "1_1") (pintype "passive"))
      (node (ref "SV32") (pin "19") (pinfunction "19_19") (pintype "passive"))
    )
    (net (code "20") (name "/VLED1") (class "Default")
      (node (ref "D1") (pin "A") (pinfunction "A_A") (pintype "passive"))
      (node (ref "SV31") (pin "12") (pinfunction "12_12") (pintype "passive"))
    )
    (net (code "21") (name "/VLED2") (class "Default")
      (node (ref "D2") (pin "A") (pinfunction "A_A") (pintype "passive"))
      (node (ref "SV31") (pin "10") (pinfunction "10_10") (pintype "passive"))
    )
    (net (code "22") (name "/VLED3") (class "Default")
      (node (ref "D3") (pin "A") (pinfunction "A_A") (pintype "passive"))
      (node (ref "SV31") (pin "13") (pinfunction "13_13") (pintype "passive"))
    )
    (net (code "23") (name "/VLED4") (class "Default")
      (node (ref "D4") (pin "A") (pinfunction "A_A") (pintype "passive"))
      (node (ref "SV31") (pin "7") (pinfunction "7_7") (pintype "passive"))
    )
    (net (code "24") (name "/VLED5") (class "Default")
      (node (ref "D5") (pin "A") (pinfunction "A_A") (pintype "passive"))
      (node (ref "SV31") (pin "14") (pinfunction "14_14") (pintype "passive"))
    )
    (net (code "25") (name "/VLED6") (class "Default")
      (node (ref "D6") (pin "A") (pinfunction "A_A") (pintype "passive"))
      (node (ref "SV31") (pin "8") (pinfunction "8_8") (pintype "passive"))
    )
    (net (code "26") (name "/VLED7") (class "Default")
      (node (ref "D7") (pin "A") (pinfunction "A_A") (pintype "passive"))
      (node (ref "SV31") (pin "15") (pinfunction "15_15") (pintype "passive"))
    )
    (net (code "27") (name "/VLED8") (class "Default")
      (node (ref "D8") (pin "A") (pinfunction "A_A") (pintype "passive"))
      (node (ref "SV31") (pin "5") (pinfunction "5_5") (pintype "passive"))
    )
    (net (code "28") (name "/VLED9") (class "Default")
      (node (ref "D9") (pin "A") (pinfunction "A_A") (pintype "passive"))
      (node (ref "SV31") (pin "16") (pinfunction "16_16") (pintype "passive"))
    )
    (net (code "29") (name "/VLED10") (class "Default")
      (node (ref "D10") (pin "A") (pinfunction "A_A") (pintype "passive"))
      (node (ref "SV31") (pin "6") (pinfunction "6_6") (pintype "passive"))
    )
    (net (code "30") (name "/VLED11") (class "Default")
      (node (ref "D11") (pin "A") (pinfunction "A_A") (pintype "passive"))
      (node (ref "SV31") (pin "17") (pinfunction "17_17") (pintype "passive"))
    )
    (net (code "31") (name "/VLED12") (class "Default")
      (node (ref "D12") (pin "A") (pinfunction "A_A") (pintype "passive"))
      (node (ref "SV31") (pin "3") (pinfunction "3_3") (pintype "passive"))
    )
    (net (code "32") (name "/VLED13") (class "Default")
      (node (ref "D13") (pin "A") (pinfunction "A_A") (pintype "passive"))
      (node (ref "SV31") (pin "18") (pinfunction "18_18") (pintype "passive"))
    )
    (net (code "33") (name "/VLED14") (class "Default")
      (node (ref "D14") (pin "A") (pinfunction "A_A") (pintype "passive"))
      (node (ref "SV31") (pin "4") (pinfunction "4_4") (pintype "passive"))
    )
    (net (code "34") (name "/VLED15") (class "Default")
      (node (ref "D15") (pin "A") (pinfunction "A_A") (pintype "passive"))
      (node (ref "SV31") (pin "19") (pinfunction "19_19") (pintype "passive"))
    )
    (net (code "35") (name "/VLED16") (class "Default")
      (node (ref "D16") (pin "A") (pinfunction "A_A") (pintype "passive"))
      (node (ref "SV31") (pin "1") (pinfunction "1_1") (pintype "passive"))
    )
    (net (code "36") (name "/VLED17") (class "Default")
      (node (ref "D17") (pin "A") (pinfunction "A_A") (pintype "passive"))
      (node (ref "SV31") (pin "20") (pinfunction "20_20") (pintype "passive"))
    )
    (net (code "37") (name "/VLED18") (class "Default")
      (node (ref "D18") (pin "A") (pinfunction "A_A") (pintype "passive"))
      (node (ref "SV31") (pin "2") (pinfunction "2_2") (pintype "passive"))
    )
  )
)
